# SH1_-_NUCLEO_HEADERS.net
KiCad netlist of a schematic drawn in Altium Designer
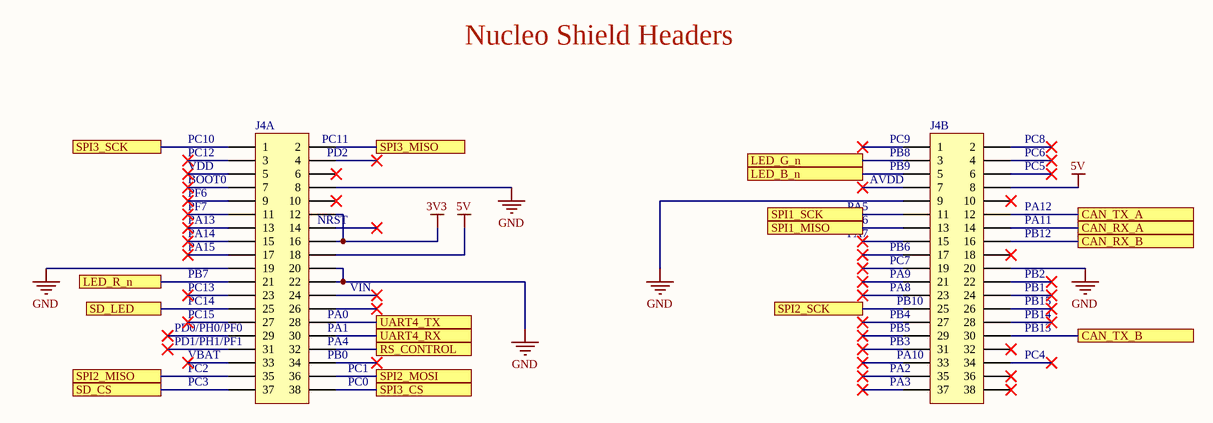
[diagram p0: SH1 - NUCLEO HEADERS.SchDoc]

(export (version "E")
  (design (tool "Eeschema 10.0.6"))
  (components
    (comp (ref "J4")
      (value "HEADER_NUCLEO")
      (footprint "HEADER_NUCLEO")
      (description "CONN HDR 38POS 0.1 GOLD PCB")
      (libsource (lib "UWRT_Schematic_Library_2020") (part "HEADER_NUCLEO"))
    )
  )
  (nets
    (net (code "1") (name "/CAN_RX_A") (class "Default")
      (node (ref "J4") (pin "52") (pinfunction "14_52") (pintype "passive"))
    )
    (net (code "2") (name "/CAN_RX_B") (class "Default")
      (node (ref "J4") (pin "54") (pinfunction "16_54") (pintype "passive"))
    )
    (net (code "3") (name "/CAN_TX_A") (class "Default")
      (node (ref "J4") (pin "50") (pinfunction "12_50") (pintype "passive"))
    )
    (net (code "4") (name "/CAN_TX_B") (class "Default")
      (node (ref "J4") (pin "68") (pinfunction "30_68") (pintype "passive"))
    )
    (net (code "5") (name "/LED_B_n") (class "Default")
      (node (ref "J4") (pin "43") (pinfunction "5_43") (pintype "passive"))
    )
    (net (code "6") (name "/LED_G_n") (class "Default")
      (node (ref "J4") (pin "41") (pinfunction "3_41") (pintype "passive"))
    )
    (net (code "7") (name "/LED_R_n") (class "Default")
      (node (ref "J4") (pin "21") (pinfunction "21_21") (pintype "passive"))
    )
    (net (code "8") (name "/RS_CONTROL") (class "Default")
      (node (ref "J4") (pin "32") (pinfunction "32_32") (pintype "passive"))
    )
    (net (code "9") (name "/SD_CS") (class "Default")
      (node (ref "J4") (pin "37") (pinfunction "37_37") (pintype "passive"))
    )
    (net (code "10") (name "/SD_LED") (class "Default")
      (node (ref "J4") (pin "25") (pinfunction "25_25") (pintype "passive"))
    )
    (net (code "11") (name "/SPI1_MISO") (class "Default")
      (node (ref "J4") (pin "51") (pinfunction "13_51") (pintype "passive"))
    )
    (net (code "12") (name "/SPI1_SCK") (class "Default")
      (node (ref "J4") (pin "49") (pinfunction "11_49") (pintype "passive"))
    )
    (net (code "13") (name "/SPI2_MISO") (class "Default")
      (node (ref "J4") (pin "35") (pinfunction "35_35") (pintype "passive"))
    )
    (net (code "14") (name "/SPI2_MOSI") (class "Default")
      (node (ref "J4") (pin "36") (pinfunction "36_36") (pintype "passive"))
    )
    (net (code "15") (name "/SPI2_SCK") (class "Default")
      (node (ref "J4") (pin "63") (pinfunction "25_63") (pintype "passive"))
    )
    (net (code "16") (name "/SPI3_CS") (class "Default")
      (node (ref "J4") (pin "38") (pinfunction "38_38") (pintype "passive"))
    )
    (net (code "17") (name "/SPI3_MISO") (class "Default")
      (node (ref "J4") (pin "2") (pinfunction "2_2") (pintype "passive"))
    )
    (net (code "18") (name "/SPI3_SCK") (class "Default")
      (node (ref "J4") (pin "1") (pinfunction "1_1") (pintype "passive"))
    )
    (net (code "19") (name "/UART4_RX") (class "Default")
      (node (ref "J4") (pin "30") (pinfunction "30_30") (pintype "passive"))
    )
    (net (code "20") (name "/UART4_TX") (class "Default")
      (node (ref "J4") (pin "28") (pinfunction "28_28") (pintype "passive"))
    )
    (net (code "21") (name "3V3") (class "Default")
      (node (ref "J4") (pin "12") (pinfunction "12_12") (pintype "passive"))
      (node (ref "J4") (pin "16") (pinfunction "16_16") (pintype "passive"))
    )
    (net (code "22") (name "5V") (class "Default")
      (node (ref "J4") (pin "18") (pinfunction "18_18") (pintype "passive"))
      (node (ref "J4") (pin "46") (pinfunction "8_46") (pintype "passive"))
    )
    (net (code "23") (name "GND") (class "Default")
      (node (ref "J4") (pin "19") (pinfunction "19_19") (pintype "passive"))
      (node (ref "J4") (pin "20") (pinfunction "20_20") (pintype "passive"))
      (node (ref "J4") (pin "22") (pinfunction "22_22") (pintype "passive"))
      (node (ref "J4") (pin "47") (pinfunction "9_47") (pintype "passive"))
      (node (ref "J4") (pin "58") (pinfunction "20_58") (pintype "passive"))
      (node (ref "J4") (pin "8") (pinfunction "8_8") (pintype "passive"))
    )
    (net (code "24") (name "unconnected-(J4-Pad3)") (class "Default")
      (node (ref "J4") (pin "3") (pinfunction "3_3") (pintype "passive+no_connect"))
    )
    (net (code "25") (name "unconnected-(J4-Pad4)") (class "Default")
      (node (ref "J4") (pin "4") (pinfunction "4_4") (pintype "passive+no_connect"))
    )
    (net (code "26") (name "unconnected-(J4-Pad5)") (class "Default")
      (node (ref "J4") (pin "5") (pinfunction "5_5") (pintype "passive+no_connect"))
    )
    (net (code "27") (name "unconnected-(J4-Pad6)") (class "Default")
      (node (ref "J4") (pin "6") (pinfunction "6_6") (pintype "passive+no_connect"))
    )
    (net (code "28") (name "unconnected-(J4-Pad7)") (class "Default")
      (node (ref "J4") (pin "7") (pinfunction "7_7") (pintype "passive+no_connect"))
    )
    (net (code "29") (name "unconnected-(J4-Pad9)") (class "Default")
      (node (ref "J4") (pin "9") (pinfunction "9_9") (pintype "passive+no_connect"))
    )
    (net (code "30") (name "unconnected-(J4-Pad10)") (class "Default")
      (node (ref "J4") (pin "10") (pinfunction "10_10") (pintype "passive+no_connect"))
    )
    (net (code "31") (name "unconnected-(J4-Pad11)") (class "Default")
      (node (ref "J4") (pin "11") (pinfunction "11_11") (pintype "passive+no_connect"))
    )
    (net (code "32") (name "unconnected-(J4-Pad13)") (class "Default")
      (node (ref "J4") (pin "13") (pinfunction "13_13") (pintype "passive+no_connect"))
    )
    (net (code "33") (name "unconnected-(J4-Pad14)") (class "Default")
      (node (ref "J4") (pin "14") (pinfunction "14_14") (pintype "passive+no_connect"))
    )
    (net (code "34") (name "unconnected-(J4-Pad15)") (class "Default")
      (node (ref "J4") (pin "15") (pinfunction "15_15") (pintype "passive+no_connect"))
    )
    (net (code "35") (name "unconnected-(J4-Pad17)") (class "Default")
      (node (ref "J4") (pin "17") (pinfunction "17_17") (pintype "passive+no_connect"))
    )
    (net (code "36") (name "unconnected-(J4-Pad23)") (class "Default")
      (node (ref "J4") (pin "23") (pinfunction "23_23") (pintype "passive+no_connect"))
    )
    (net (code "37") (name "unconnected-(J4-Pad24)") (class "Default")
      (node (ref "J4") (pin "24") (pinfunction "24_24") (pintype "passive+no_connect"))
    )
    (net (code "38") (name "unconnected-(J4-Pad26)") (class "Default")
      (node (ref "J4") (pin "26") (pinfunction "26_26") (pintype "passive+no_connect"))
    )
    (net (code "39") (name "unconnected-(J4-Pad27)") (class "Default")
      (node (ref "J4") (pin "27") (pinfunction "27_27") (pintype "passive+no_connect"))
    )
    (net (code "40") (name "unconnected-(J4-Pad29)") (class "Default")
      (node (ref "J4") (pin "29") (pinfunction "29_29") (pintype "passive+no_connect"))
    )
    (net (code "41") (name "unconnected-(J4-Pad31)") (class "Default")
      (node (ref "J4") (pin "31") (pinfunction "31_31") (pintype "passive+no_connect"))
    )
    (net (code "42") (name "unconnected-(J4-Pad33)") (class "Default")
      (node (ref "J4") (pin "33") (pinfunction "33_33") (pintype "passive+no_connect"))
    )
    (net (code "43") (name "unconnected-(J4-Pad34)") (class "Default")
      (node (ref "J4") (pin "34") (pinfunction "34_34") (pintype "passive+no_connect"))
    )
    (net (code "44") (name "unconnected-(J4B-1-Pad39)") (class "Default")
      (node (ref "J4") (pin "39") (pinfunction "1_39") (pintype "passive+no_connect"))
    )
    (net (code "45") (name "unconnected-(J4B-2-Pad40)") (class "Default")
      (node (ref "J4") (pin "40") (pinfunction "2_40") (pintype "passive+no_connect"))
    )
    (net (code "46") (name "unconnected-(J4B-4-Pad42)") (class "Default")
      (node (ref "J4") (pin "42") (pinfunction "4_42") (pintype "passive+no_connect"))
    )
    (net (code "47") (name "unconnected-(J4B-6-Pad44)") (class "Default")
      (node (ref "J4") (pin "44") (pinfunction "6_44") (pintype "passive+no_connect"))
    )
    (net (code "48") (name "unconnected-(J4B-7-Pad45)") (class "Default")
      (node (ref "J4") (pin "45") (pinfunction "7_45") (pintype "passive+no_connect"))
    )
    (net (code "49") (name "unconnected-(J4B-10-Pad48)") (class "Default")
      (node (ref "J4") (pin "48") (pinfunction "10_48") (pintype "passive+no_connect"))
    )
    (net (code "50") (name "unconnected-(J4B-15-Pad53)") (class "Default")
      (node (ref "J4") (pin "53") (pinfunction "15_53") (pintype "passive+no_connect"))
    )
    (net (code "51") (name "unconnected-(J4B-17-Pad55)") (class "Default")
      (node (ref "J4") (pin "55") (pinfunction "17_55") (pintype "passive+no_connect"))
    )
    (net (code "52") (name "unconnected-(J4B-18-Pad56)") (class "Default")
      (node (ref "J4") (pin "56") (pinfunction "18_56") (pintype "passive+no_connect"))
    )
    (net (code "53") (name "unconnected-(J4B-19-Pad57)") (class "Default")
      (node (ref "J4") (pin "57") (pinfunction "19_57") (pintype "passive+no_connect"))
    )
    (net (code "54") (name "unconnected-(J4B-21-Pad59)") (class "Default")
      (node (ref "J4") (pin "59") (pinfunction "21_59") (pintype "passive+no_connect"))
    )
    (net (code "55") (name "unconnected-(J4B-22-Pad60)") (class "Default")
      (node (ref "J4") (pin "60") (pinfunction "22_60") (pintype "passive+no_connect"))
    )
    (net (code "56") (name "unconnected-(J4B-23-Pad61)") (class "Default")
      (node (ref "J4") (pin "61") (pinfunction "23_61") (pintype "passive+no_connect"))
    )
    (net (code "57") (name "unconnected-(J4B-24-Pad62)") (class "Default")
      (node (ref "J4") (pin "62") (pinfunction "24_62") (pintype "passive+no_connect"))
    )
    (net (code "58") (name "unconnected-(J4B-26-Pad64)") (class "Default")
      (node (ref "J4") (pin "64") (pinfunction "26_64") (pintype "passive+no_connect"))
    )
    (net (code "59") (name "unconnected-(J4B-27-Pad65)") (class "Default")
      (node (ref "J4") (pin "65") (pinfunction "27_65") (pintype "passive+no_connect"))
    )
    (net (code "60") (name "unconnected-(J4B-28-Pad66)") (class "Default")
      (node (ref "J4") (pin "66") (pinfunction "28_66") (pintype "passive+no_connect"))
    )
    (net (code "61") (name "unconnected-(J4B-29-Pad67)") (class "Default")
      (node (ref "J4") (pin "67") (pinfunction "29_67") (pintype "passive+no_connect"))
    )
    (net (code "62") (name "unconnected-(J4B-31-Pad69)") (class "Default")
      (node (ref "J4") (pin "69") (pinfunction "31_69") (pintype "passive+no_connect"))
    )
    (net (code "63") (name "unconnected-(J4B-32-Pad70)") (class "Default")
      (node (ref "J4") (pin "70") (pinfunction "32_70") (pintype "passive+no_connect"))
    )
    (net (code "64") (name "unconnected-(J4B-33-Pad71)") (class "Default")
      (node (ref "J4") (pin "71") (pinfunction "33_71") (pintype "passive+no_connect"))
    )
    (net (code "65") (name "unconnected-(J4B-34-Pad72)") (class "Default")
      (node (ref "J4") (pin "72") (pinfunction "34_72") (pintype "passive+no_connect"))
    )
    (net (code "66") (name "unconnected-(J4B-35-Pad73)") (class "Default")
      (node (ref "J4") (pin "73") (pinfunction "35_73") (pintype "passive+no_connect"))
    )
    (net (code "67") (name "unconnected-(J4B-36-Pad74)") (class "Default")
      (node (ref "J4") (pin "74") (pinfunction "36_74") (pintype "passive+no_connect"))
    )
    (net (code "68") (name "unconnected-(J4B-37-Pad75)") (class "Default")
      (node (ref "J4") (pin "75") (pinfunction "37_75") (pintype "passive+no_connect"))
    )
    (net (code "69") (name "unconnected-(J4B-38-Pad76)") (class "Default")
      (node (ref "J4") (pin "76") (pinfunction "38_76") (pintype "passive+no_connect"))
    )
  )
)
